# bspd.net
KiCad netlist of a schematic drawn in Altium Designer
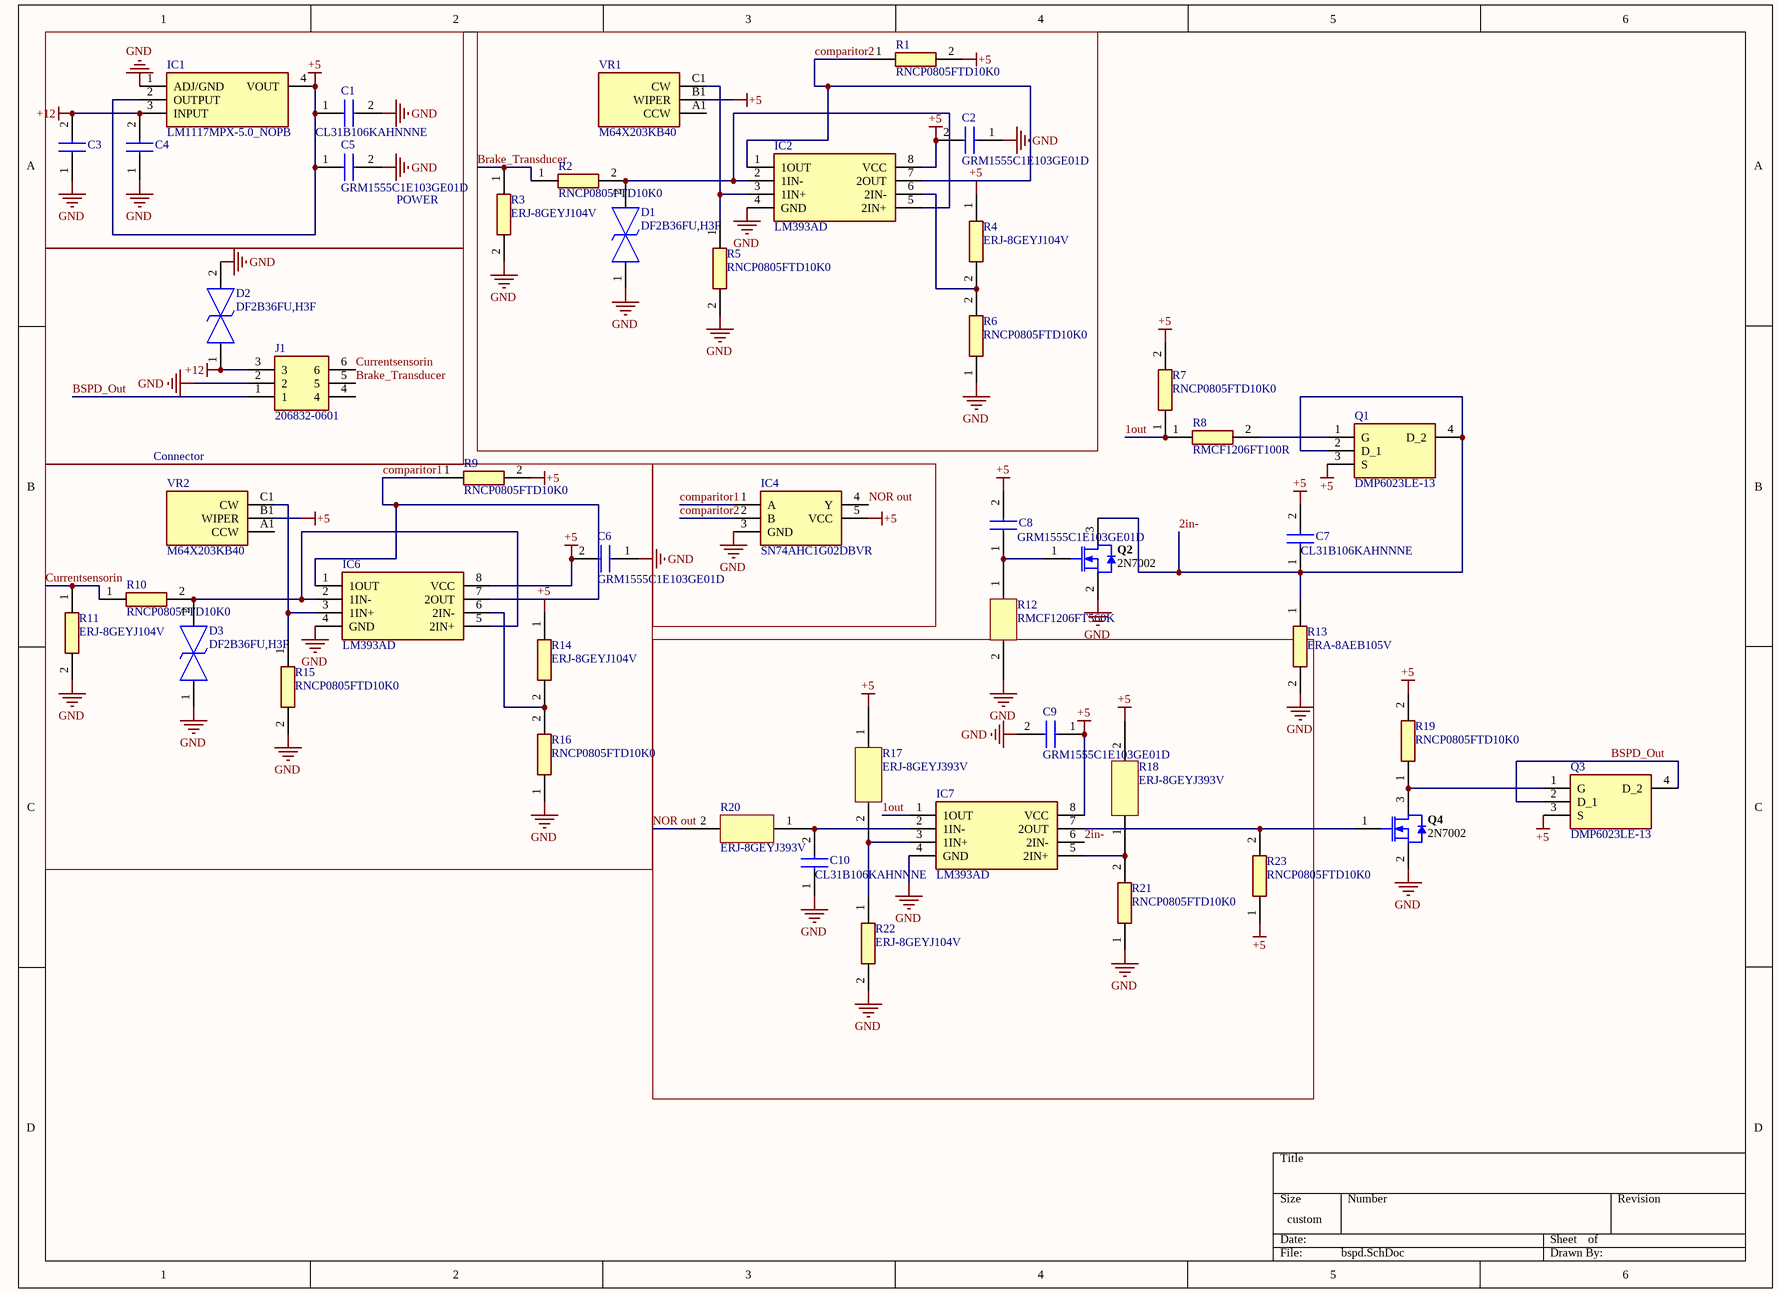
[diagram p0: bspd.SchDoc]

(export (version "E")
  (design (tool "Eeschema 10.0.6"))
  (components
    (comp (ref "C1")
      (value "CL31B106KAHNNNE")
      (footprint "SamacSys:CAPC3216X180N")
      (description "Capacitor")
      (fields (field (name "MOUSER PART NUMBER") "187-CL31B106KAHNNNE"))
      (libsource (lib "*") (part "CL31B106KAHNNNE"))
    )
    (comp (ref "C2")
      (value "GRM1555C1E103GE01D")
      (footprint "SamacSys:CAPC1005X55N")
      (description "Capacitor")
      (fields (field (name "MOUSER PART NUMBER") "81-GRM1555C1E103GE1D"))
      (libsource (lib "*") (part "GRM1555C1E103GE01D"))
    )
    (comp (ref "C3")
      (value "CL31B106KAHNNNE")
      (footprint "SamacSys:CAPC3216X180N")
      (description "Capacitor")
      (fields (field (name "MOUSER PART NUMBER") "187-CL31B106KAHNNNE"))
      (libsource (lib "*") (part "CL31B106KAHNNNE"))
    )
    (comp (ref "C4")
      (value "GRM1555C1E103GE01D")
      (footprint "SamacSys:CAPC1005X55N")
      (description "Capacitor")
      (fields (field (name "MOUSER PART NUMBER") "81-GRM1555C1E103GE1D"))
      (libsource (lib "*") (part "GRM1555C1E103GE01D"))
    )
    (comp (ref "C5")
      (value "GRM1555C1E103GE01D")
      (footprint "SamacSys:CAPC1005X55N")
      (description "Capacitor")
      (fields (field (name "MOUSER PART NUMBER") "81-GRM1555C1E103GE1D"))
      (libsource (lib "*") (part "GRM1555C1E103GE01D"))
    )
    (comp (ref "C6")
      (value "GRM1555C1E103GE01D")
      (footprint "SamacSys:CAPC1005X55N")
      (description "Capacitor")
      (fields (field (name "MOUSER PART NUMBER") "81-GRM1555C1E103GE1D"))
      (libsource (lib "*") (part "GRM1555C1E103GE01D"))
    )
    (comp (ref "C7")
      (value "CL31B106KAHNNNE")
      (footprint "SamacSys:CAPC3216X180N")
      (description "Capacitor")
      (fields (field (name "MOUSER PART NUMBER") "187-CL31B106KAHNNNE"))
      (libsource (lib "*") (part "CL31B106KAHNNNE"))
    )
    (comp (ref "C8")
      (value "GRM1555C1E103GE01D")
      (footprint "SamacSys:CAPC1005X55N")
      (description "Capacitor")
      (fields (field (name "MOUSER PART NUMBER") "81-GRM1555C1E103GE1D"))
      (libsource (lib "*") (part "GRM1555C1E103GE01D"))
    )
    (comp (ref "C9")
      (value "GRM1555C1E103GE01D")
      (footprint "SamacSys:CAPC1005X55N")
      (description "Capacitor")
      (fields (field (name "MOUSER PART NUMBER") "81-GRM1555C1E103GE1D"))
      (libsource (lib "*") (part "GRM1555C1E103GE01D"))
    )
    (comp (ref "C10")
      (value "CL31B106KAHNNNE")
      (footprint "SamacSys:CAPC3216X180N")
      (description "Capacitor")
      (fields (field (name "MOUSER PART NUMBER") "187-CL31B106KAHNNNE"))
      (libsource (lib "*") (part "CL31B106KAHNNNE"))
    )
    (comp (ref "D1")
      (value "DF2B36FU,H3F")
      (footprint "SamacSys:1SS357TPH3F")
      (description "TVS Diode (Bi-directional)")
      (fields (field (name "MOUSER PART NUMBER") "757-DF2B36FUH3F"))
      (libsource (lib "*") (part "DF2B36FU,H3F"))
    )
    (comp (ref "D2")
      (value "DF2B36FU,H3F")
      (footprint "SamacSys:1SS357TPH3F")
      (description "TVS Diode (Bi-directional)")
      (fields (field (name "MOUSER PART NUMBER") "757-DF2B36FUH3F"))
      (libsource (lib "*") (part "DF2B36FU,H3F"))
    )
    (comp (ref "D3")
      (value "DF2B36FU,H3F")
      (footprint "SamacSys:1SS357TPH3F")
      (description "TVS Diode (Bi-directional)")
      (fields (field (name "MOUSER PART NUMBER") "757-DF2B36FUH3F"))
      (libsource (lib "*") (part "DF2B36FU,H3F"))
    )
    (comp (ref "IC1")
      (value "LM1117MPX-5.0_NOPB")
      (footprint "SamacSys:SOT230P700X180-4N")
      (description "Integrated Circuit")
      (fields
        (field (name "MANUFACTURER_PART_NUMBER") "LM1117MPX-5.0/NOPB")
        (field (name "MOUSER PART NUMBER") "926-LM1117MPX5.0NOPB")
      )
      (libsource (lib "*") (part "LM1117MPX-5.0_NOPB"))
    )
    (comp (ref "IC2")
      (value "LM393AD")
      (footprint "SamacSys:SOIC127P600X175-8N")
      (description "Integrated Circuit")
      (fields (field (name "MOUSER PART NUMBER") "595-LM393AD"))
      (libsource (lib "*") (part "LM393AD"))
    )
    (comp (ref "IC4")
      (value "SN74AHC1G02DBVR")
      (footprint "SamacSys:SOT95P280X145-5N")
      (description "Integrated Circuit")
      (fields (field (name "MOUSER PART NUMBER") "595-SN74AHC1G02DBVR"))
      (libsource (lib "*") (part "SN74AHC1G02DBVR"))
    )
    (comp (ref "IC6")
      (value "LM393AD")
      (footprint "SamacSys:SOIC127P600X175-8N")
      (description "Integrated Circuit")
      (fields (field (name "MOUSER PART NUMBER") "595-LM393AD"))
      (libsource (lib "*") (part "LM393AD"))
    )
    (comp (ref "IC7")
      (value "LM393AD")
      (footprint "SamacSys:SOIC127P600X175-8N")
      (description "Integrated Circuit")
      (fields (field (name "MOUSER PART NUMBER") "595-LM393AD"))
      (libsource (lib "*") (part "LM393AD"))
    )
    (comp (ref "J1")
      (value "206832-0601")
      (footprint "SamacSys:2068320601")
      (description "Connector")
      (fields (field (name "MOUSER PART NUMBER") "538-206832-0601"))
      (libsource (lib "SamacSys") (part "206832-0601"))
    )
    (comp (ref "Q1")
      (value "DMP6023LE-13")
      (footprint "SamacSys:SOT230P700X165-4N")
      (description "MOSFET (P-Channel)")
      (fields (field (name "MOUSER PART NUMBER") "621-DMP6023LE-13"))
      (libsource (lib "*") (part "DMP6023LE-13"))
    )
    (comp (ref "Q2")
      (value "2N7002")
      (footprint "INF-PG-SOT23_M")
      (fields (field (name "MANUFACTURER") "Infineon"))
      (libsource (lib "Altium Content Vault") (part "INF-NDMOS-GSD-3"))
    )
    (comp (ref "Q3")
      (value "DMP6023LE-13")
      (footprint "SamacSys:SOT230P700X165-4N")
      (description "MOSFET (P-Channel)")
      (fields (field (name "MOUSER PART NUMBER") "621-DMP6023LE-13"))
      (libsource (lib "*") (part "DMP6023LE-13"))
    )
    (comp (ref "Q4")
      (value "2N7002")
      (footprint "INF-PG-SOT23_M")
      (fields (field (name "MANUFACTURER") "Infineon"))
      (libsource (lib "Altium Content Vault") (part "INF-NDMOS-GSD-3"))
    )
    (comp (ref "R1")
      (value "RNCP0805FTD10K0")
      (footprint "SamacSys:RESC2012X65N")
      (description "Resistor")
      (libsource (lib "") (part "RNCP0805FTD10K0_1"))
    )
    (comp (ref "R2")
      (value "RNCP0805FTD10K0")
      (footprint "SamacSys:RESC2012X65N")
      (description "Resistor")
      (libsource (lib "") (part "RNCP0805FTD10K0_1"))
    )
    (comp (ref "R3")
      (value "ERJ-8GEYJ104V")
      (footprint "SamacSys:RESC3116X70N")
      (description "Resistor")
      (fields (field (name "MOUSER PART NUMBER") "667-ERJ-8GEYJ104V"))
      (libsource (lib "*") (part "ERJ-8GEYJ104V"))
    )
    (comp (ref "R4")
      (value "ERJ-8GEYJ104V")
      (footprint "SamacSys:RESC3116X70N")
      (description "Resistor")
      (fields (field (name "MOUSER PART NUMBER") "667-ERJ-8GEYJ104V"))
      (libsource (lib "*") (part "ERJ-8GEYJ104V"))
    )
    (comp (ref "R5")
      (value "RNCP0805FTD10K0")
      (footprint "SamacSys:RESC2012X65N")
      (description "Resistor")
      (libsource (lib "") (part "RNCP0805FTD10K0_2"))
    )
    (comp (ref "R6")
      (value "RNCP0805FTD10K0")
      (footprint "SamacSys:RESC2012X65N")
      (description "Resistor")
      (libsource (lib "*") (part "RNCP0805FTD10K0"))
    )
    (comp (ref "R7")
      (value "RNCP0805FTD10K0")
      (footprint "SamacSys:RESC2012X65N")
      (description "Resistor")
      (libsource (lib "*") (part "RNCP0805FTD10K0"))
    )
    (comp (ref "R8")
      (value "RMCF1206FT100R")
      (footprint "SamacSys:RESC3216X70N")
      (description "Resistor")
      (libsource (lib "*") (part "RMCF1206FT100R"))
    )
    (comp (ref "R9")
      (value "RNCP0805FTD10K0")
      (footprint "SamacSys:RESC2012X65N")
      (description "Resistor")
      (libsource (lib "") (part "RNCP0805FTD10K0_1"))
    )
    (comp (ref "R10")
      (value "RNCP0805FTD10K0")
      (footprint "SamacSys:RESC2012X65N")
      (description "Resistor")
      (libsource (lib "") (part "RNCP0805FTD10K0_1"))
    )
    (comp (ref "R11")
      (value "ERJ-8GEYJ104V")
      (footprint "SamacSys:RESC3116X70N")
      (description "Resistor")
      (fields (field (name "MOUSER PART NUMBER") "667-ERJ-8GEYJ104V"))
      (libsource (lib "*") (part "ERJ-8GEYJ104V"))
    )
    (comp (ref "R12")
      (value "RMCF1206FT560K")
      (footprint "RMCF1206FT560K")
      (description "560k smd 1/4 w resistor")
      (libsource (lib "SamacSys") (part "RMCF1206FT560K"))
    )
    (comp (ref "R13")
      (value "ERA-8AEB105V")
      (footprint "SamacSys:ERA8A_(0805)")
      (description "Resistor")
      (fields (field (name "MOUSER PART NUMBER") "667-ERA-8AEB105V"))
      (libsource (lib "*") (part "ERA-8AEB105V"))
    )
    (comp (ref "R14")
      (value "ERJ-8GEYJ104V")
      (footprint "SamacSys:RESC3116X70N")
      (description "Resistor")
      (fields (field (name "MOUSER PART NUMBER") "667-ERJ-8GEYJ104V"))
      (libsource (lib "*") (part "ERJ-8GEYJ104V"))
    )
    (comp (ref "R15")
      (value "RNCP0805FTD10K0")
      (footprint "SamacSys:RESC2012X65N")
      (description "Resistor")
      (libsource (lib "") (part "RNCP0805FTD10K0_2"))
    )
    (comp (ref "R16")
      (value "RNCP0805FTD10K0")
      (footprint "SamacSys:RESC2012X65N")
      (description "Resistor")
      (libsource (lib "*") (part "RNCP0805FTD10K0"))
    )
    (comp (ref "R17")
      (value "ERJ-8GEYJ393V")
      (footprint "ERJ-8GEYJ393V")
      (libsource (lib "SamacSys") (part "ERJ-8GEYJ393V"))
    )
    (comp (ref "R18")
      (value "ERJ-8GEYJ393V")
      (footprint "ERJ-8GEYJ393V")
      (libsource (lib "") (part "ERJ-8GEYJ393V_2"))
    )
    (comp (ref "R19")
      (value "RNCP0805FTD10K0")
      (footprint "SamacSys:RESC2012X65N")
      (description "Resistor")
      (libsource (lib "*") (part "RNCP0805FTD10K0"))
    )
    (comp (ref "R20")
      (value "ERJ-8GEYJ393V")
      (footprint "ERJ-8GEYJ393V")
      (libsource (lib "") (part "ERJ-8GEYJ393V_1"))
    )
    (comp (ref "R21")
      (value "RNCP0805FTD10K0")
      (footprint "SamacSys:RESC2012X65N")
      (description "Resistor")
      (libsource (lib "*") (part "RNCP0805FTD10K0"))
    )
    (comp (ref "R22")
      (value "ERJ-8GEYJ104V")
      (footprint "SamacSys:RESC3116X70N")
      (description "Resistor")
      (fields (field (name "MOUSER PART NUMBER") "667-ERJ-8GEYJ104V"))
      (libsource (lib "*") (part "ERJ-8GEYJ104V"))
    )
    (comp (ref "R23")
      (value "RNCP0805FTD10K0")
      (footprint "SamacSys:RESC2012X65N")
      (description "Resistor")
      (libsource (lib "*") (part "RNCP0805FTD10K0"))
    )
    (comp (ref "VR1")
      (value "M64X203KB40")
      (footprint "SamacSys:M64X203KB40")
      (description "Variable Resistor")
      (fields (field (name "MOUSER PART NUMBER") "594-64X203"))
      (libsource (lib "*") (part "M64X203KB40"))
    )
    (comp (ref "VR2")
      (value "M64X203KB40")
      (footprint "SamacSys:M64X203KB40")
      (description "Variable Resistor")
      (fields (field (name "MOUSER PART NUMBER") "594-64X203"))
      (libsource (lib "*") (part "M64X203KB40"))
    )
  )
  (nets
    (net (code "1") (name "+5") (class "Default")
      (node (ref "C1") (pin "1") (pinfunction "1_1") (pintype "passive"))
      (node (ref "C2") (pin "2") (pinfunction "2_2") (pintype "passive"))
      (node (ref "C5") (pin "1") (pinfunction "1_1") (pintype "passive"))
      (node (ref "C6") (pin "2") (pinfunction "2_2") (pintype "passive"))
      (node (ref "C7") (pin "2") (pinfunction "2_2") (pintype "passive"))
      (node (ref "C8") (pin "2") (pinfunction "2_2") (pintype "passive"))
      (node (ref "C9") (pin "1") (pinfunction "1_1") (pintype "passive"))
      (node (ref "IC1") (pin "2") (pinfunction "OUTPUT_2") (pintype "passive"))
      (node (ref "IC1") (pin "4") (pinfunction "VOUT_4") (pintype "passive"))
      (node (ref "IC2") (pin "8") (pinfunction "VCC_8") (pintype "passive"))
      (node (ref "IC4") (pin "5") (pinfunction "VCC_5") (pintype "passive"))
      (node (ref "IC6") (pin "8") (pinfunction "VCC_8") (pintype "passive"))
      (node (ref "IC7") (pin "8") (pinfunction "VCC_8") (pintype "passive"))
      (node (ref "Q1") (pin "3") (pinfunction "S_3") (pintype "passive"))
      (node (ref "Q3") (pin "3") (pinfunction "S_3") (pintype "passive"))
      (node (ref "R1") (pin "2") (pinfunction "2_2") (pintype "passive"))
      (node (ref "R14") (pin "1") (pinfunction "1_1") (pintype "passive"))
      (node (ref "R17") (pin "1") (pinfunction "1_1") (pintype "passive"))
      (node (ref "R18") (pin "2") (pinfunction "2_2") (pintype "passive"))
      (node (ref "R19") (pin "2") (pinfunction "2_2") (pintype "passive"))
      (node (ref "R23") (pin "1") (pinfunction "1_1") (pintype "passive"))
      (node (ref "R4") (pin "1") (pinfunction "1_1") (pintype "passive"))
      (node (ref "R7") (pin "2") (pinfunction "2_2") (pintype "passive"))
      (node (ref "R9") (pin "2") (pinfunction "2_2") (pintype "passive"))
      (node (ref "VR1") (pin "B1") (pinfunction "WIPER_B1") (pintype "passive"))
      (node (ref "VR2") (pin "B1") (pinfunction "WIPER_B1") (pintype "passive"))
    )
    (net (code "2") (name "+12") (class "Default")
      (node (ref "C3") (pin "2") (pinfunction "2_2") (pintype "passive"))
      (node (ref "C4") (pin "2") (pinfunction "2_2") (pintype "passive"))
      (node (ref "D2") (pin "1") (pinfunction "1_1") (pintype "passive"))
      (node (ref "IC1") (pin "3") (pinfunction "INPUT_3") (pintype "passive"))
      (node (ref "J1") (pin "3") (pinfunction "3_3") (pintype "passive"))
    )
    (net (code "3") (name "/1out") (class "Default")
      (node (ref "IC7") (pin "1") (pinfunction "1OUT_1") (pintype "passive"))
      (node (ref "R7") (pin "1") (pinfunction "1_1") (pintype "passive"))
      (node (ref "R8") (pin "1") (pinfunction "1_1") (pintype "passive"))
    )
    (net (code "4") (name "/2in-") (class "Default")
      (node (ref "C7") (pin "1") (pinfunction "1_1") (pintype "passive"))
      (node (ref "IC7") (pin "6") (pinfunction "2IN-_6") (pintype "passive"))
      (node (ref "Q1") (pin "2") (pinfunction "D_1_2") (pintype "passive"))
      (node (ref "Q1") (pin "4") (pinfunction "D_2_4") (pintype "passive"))
      (node (ref "Q2") (pin "3") (pinfunction "DRAIN_3") (pintype "passive"))
      (node (ref "R13") (pin "1") (pinfunction "1_1") (pintype "passive"))
    )
    (net (code "5") (name "/BSPD_Out") (class "Default")
      (node (ref "J1") (pin "1") (pinfunction "1_1") (pintype "passive"))
      (node (ref "Q3") (pin "2") (pinfunction "D_1_2") (pintype "passive"))
      (node (ref "Q3") (pin "4") (pinfunction "D_2_4") (pintype "passive"))
    )
    (net (code "6") (name "/Brake_Transducer") (class "Default")
      (node (ref "J1") (pin "5") (pinfunction "5_5") (pintype "passive"))
      (node (ref "R2") (pin "1") (pinfunction "1_1") (pintype "passive"))
      (node (ref "R3") (pin "1") (pinfunction "1_1") (pintype "passive"))
    )
    (net (code "7") (name "/Currentsensorin") (class "Default")
      (node (ref "J1") (pin "6") (pinfunction "6_6") (pintype "passive"))
      (node (ref "R10") (pin "1") (pinfunction "1_1") (pintype "passive"))
      (node (ref "R11") (pin "1") (pinfunction "1_1") (pintype "passive"))
    )
    (net (code "8") (name "/NOR out") (class "Default")
      (node (ref "IC4") (pin "4") (pinfunction "Y_4") (pintype "passive"))
      (node (ref "R20") (pin "2") (pinfunction "2_2") (pintype "passive"))
    )
    (net (code "9") (name "/comparitor1") (class "Default")
      (node (ref "IC4") (pin "1") (pinfunction "A_1") (pintype "passive"))
      (node (ref "IC6") (pin "1") (pinfunction "1OUT_1") (pintype "passive"))
      (node (ref "IC6") (pin "7") (pinfunction "2OUT_7") (pintype "passive"))
      (node (ref "R9") (pin "1") (pinfunction "1_1") (pintype "passive"))
    )
    (net (code "10") (name "/comparitor2") (class "Default")
      (node (ref "IC2") (pin "1") (pinfunction "1OUT_1") (pintype "passive"))
      (node (ref "IC2") (pin "7") (pinfunction "2OUT_7") (pintype "passive"))
      (node (ref "IC4") (pin "2") (pinfunction "B_2") (pintype "passive"))
      (node (ref "R1") (pin "1") (pinfunction "1_1") (pintype "passive"))
    )
    (net (code "11") (name "GND") (class "Default")
      (node (ref "C1") (pin "2") (pinfunction "2_2") (pintype "passive"))
      (node (ref "C10") (pin "1") (pinfunction "1_1") (pintype "passive"))
      (node (ref "C2") (pin "1") (pinfunction "1_1") (pintype "passive"))
      (node (ref "C3") (pin "1") (pinfunction "1_1") (pintype "passive"))
      (node (ref "C4") (pin "1") (pinfunction "1_1") (pintype "passive"))
      (node (ref "C5") (pin "2") (pinfunction "2_2") (pintype "passive"))
      (node (ref "C6") (pin "1") (pinfunction "1_1") (pintype "passive"))
      (node (ref "C9") (pin "2") (pinfunction "2_2") (pintype "passive"))
      (node (ref "D1") (pin "1") (pinfunction "1_1") (pintype "passive"))
      (node (ref "D2") (pin "2") (pinfunction "2_2") (pintype "passive"))
      (node (ref "D3") (pin "1") (pinfunction "1_1") (pintype "passive"))
      (node (ref "IC1") (pin "1") (pinfunction "ADJ/GND_1") (pintype "passive"))
      (node (ref "IC2") (pin "4") (pinfunction "GND_4") (pintype "passive"))
      (node (ref "IC4") (pin "3") (pinfunction "GND_3") (pintype "passive"))
      (node (ref "IC6") (pin "4") (pinfunction "GND_4") (pintype "passive"))
      (node (ref "IC7") (pin "4") (pinfunction "GND_4") (pintype "passive"))
      (node (ref "J1") (pin "2") (pinfunction "2_2") (pintype "passive"))
      (node (ref "Q2") (pin "2") (pinfunction "SOURCE_2") (pintype "passive"))
      (node (ref "Q4") (pin "2") (pinfunction "SOURCE_2") (pintype "passive"))
      (node (ref "R11") (pin "2") (pinfunction "2_2") (pintype "passive"))
      (node (ref "R12") (pin "2") (pinfunction "2_2") (pintype "passive"))
      (node (ref "R13") (pin "2") (pinfunction "2_2") (pintype "passive"))
      (node (ref "R15") (pin "2") (pinfunction "2_2") (pintype "passive"))
      (node (ref "R16") (pin "1") (pinfunction "1_1") (pintype "passive"))
      (node (ref "R21") (pin "1") (pinfunction "1_1") (pintype "passive"))
      (node (ref "R22") (pin "2") (pinfunction "2_2") (pintype "passive"))
      (node (ref "R3") (pin "2") (pinfunction "2_2") (pintype "passive"))
      (node (ref "R5") (pin "2") (pinfunction "2_2") (pintype "passive"))
      (node (ref "R6") (pin "1") (pinfunction "1_1") (pintype "passive"))
    )
    (net (code "12") (name "Net-(IC2-1IN+)") (class "Default")
      (node (ref "IC2") (pin "3") (pinfunction "1IN+_3") (pintype "passive"))
      (node (ref "R5") (pin "1") (pinfunction "1_1") (pintype "passive"))
      (node (ref "VR1") (pin "C1") (pinfunction "CW_C1") (pintype "passive"))
    )
    (net (code "13") (name "Net-(IC2-1IN-)") (class "Default")
      (node (ref "D1") (pin "2") (pinfunction "2_2") (pintype "passive"))
      (node (ref "IC2") (pin "2") (pinfunction "1IN-_2") (pintype "passive"))
      (node (ref "IC2") (pin "5") (pinfunction "2IN+_5") (pintype "passive"))
      (node (ref "R2") (pin "2") (pinfunction "2_2") (pintype "passive"))
    )
    (net (code "14") (name "Net-(IC2-2IN-)") (class "Default")
      (node (ref "IC2") (pin "6") (pinfunction "2IN-_6") (pintype "passive"))
      (node (ref "R4") (pin "2") (pinfunction "2_2") (pintype "passive"))
      (node (ref "R6") (pin "2") (pinfunction "2_2") (pintype "passive"))
    )
    (net (code "15") (name "Net-(IC6-1IN+)") (class "Default")
      (node (ref "IC6") (pin "3") (pinfunction "1IN+_3") (pintype "passive"))
      (node (ref "R15") (pin "1") (pinfunction "1_1") (pintype "passive"))
      (node (ref "VR2") (pin "C1") (pinfunction "CW_C1") (pintype "passive"))
    )
    (net (code "16") (name "Net-(IC6-1IN-)") (class "Default")
      (node (ref "D3") (pin "2") (pinfunction "2_2") (pintype "passive"))
      (node (ref "IC6") (pin "2") (pinfunction "1IN-_2") (pintype "passive"))
      (node (ref "IC6") (pin "5") (pinfunction "2IN+_5") (pintype "passive"))
      (node (ref "R10") (pin "2") (pinfunction "2_2") (pintype "passive"))
    )
    (net (code "17") (name "Net-(IC6-2IN-)") (class "Default")
      (node (ref "IC6") (pin "6") (pinfunction "2IN-_6") (pintype "passive"))
      (node (ref "R14") (pin "2") (pinfunction "2_2") (pintype "passive"))
      (node (ref "R16") (pin "2") (pinfunction "2_2") (pintype "passive"))
    )
    (net (code "18") (name "Net-(IC7-1IN+)") (class "Default")
      (node (ref "IC7") (pin "3") (pinfunction "1IN+_3") (pintype "passive"))
      (node (ref "R17") (pin "2") (pinfunction "2_2") (pintype "passive"))
      (node (ref "R22") (pin "1") (pinfunction "1_1") (pintype "passive"))
    )
    (net (code "19") (name "Net-(IC7-1IN-)") (class "Default")
      (node (ref "C10") (pin "2") (pinfunction "2_2") (pintype "passive"))
      (node (ref "IC7") (pin "2") (pinfunction "1IN-_2") (pintype "passive"))
      (node (ref "R20") (pin "1") (pinfunction "1_1") (pintype "passive"))
    )
    (net (code "20") (name "Net-(IC7-2IN+)") (class "Default")
      (node (ref "IC7") (pin "5") (pinfunction "2IN+_5") (pintype "passive"))
      (node (ref "R18") (pin "1") (pinfunction "1_1") (pintype "passive"))
      (node (ref "R21") (pin "2") (pinfunction "2_2") (pintype "passive"))
    )
    (net (code "21") (name "Net-(IC7-2OUT)") (class "Default")
      (node (ref "IC7") (pin "7") (pinfunction "2OUT_7") (pintype "passive"))
      (node (ref "Q4") (pin "1") (pinfunction "GATE_1") (pintype "passive"))
      (node (ref "R23") (pin "2") (pinfunction "2_2") (pintype "passive"))
    )
    (net (code "22") (name "Net-(Q1-G)") (class "Default")
      (node (ref "Q1") (pin "1") (pinfunction "G_1") (pintype "passive"))
      (node (ref "R8") (pin "2") (pinfunction "2_2") (pintype "passive"))
    )
    (net (code "23") (name "Net-(Q2-GATE)") (class "Default")
      (node (ref "C8") (pin "1") (pinfunction "1_1") (pintype "passive"))
      (node (ref "Q2") (pin "1") (pinfunction "GATE_1") (pintype "passive"))
      (node (ref "R12") (pin "1") (pinfunction "1_1") (pintype "passive"))
    )
    (net (code "24") (name "Net-(Q3-G)") (class "Default")
      (node (ref "Q3") (pin "1") (pinfunction "G_1") (pintype "passive"))
      (node (ref "Q4") (pin "3") (pinfunction "DRAIN_3") (pintype "passive"))
      (node (ref "R19") (pin "1") (pinfunction "1_1") (pintype "passive"))
    )
    (net (code "25") (name "unconnected-(J1-Pad4)") (class "Default")
      (node (ref "J1") (pin "4") (pinfunction "4_4") (pintype "passive"))
    )
    (net (code "26") (name "unconnected-(VR1-CCW-PadA1)") (class "Default")
      (node (ref "VR1") (pin "A1") (pinfunction "CCW_A1") (pintype "passive"))
    )
    (net (code "27") (name "unconnected-(VR2-CCW-PadA1)") (class "Default")
      (node (ref "VR2") (pin "A1") (pinfunction "CCW_A1") (pintype "passive"))
    )
  )
)
